# Sheet1_Auto_sedzia.net
KiCad netlist of a schematic drawn in Altium Designer
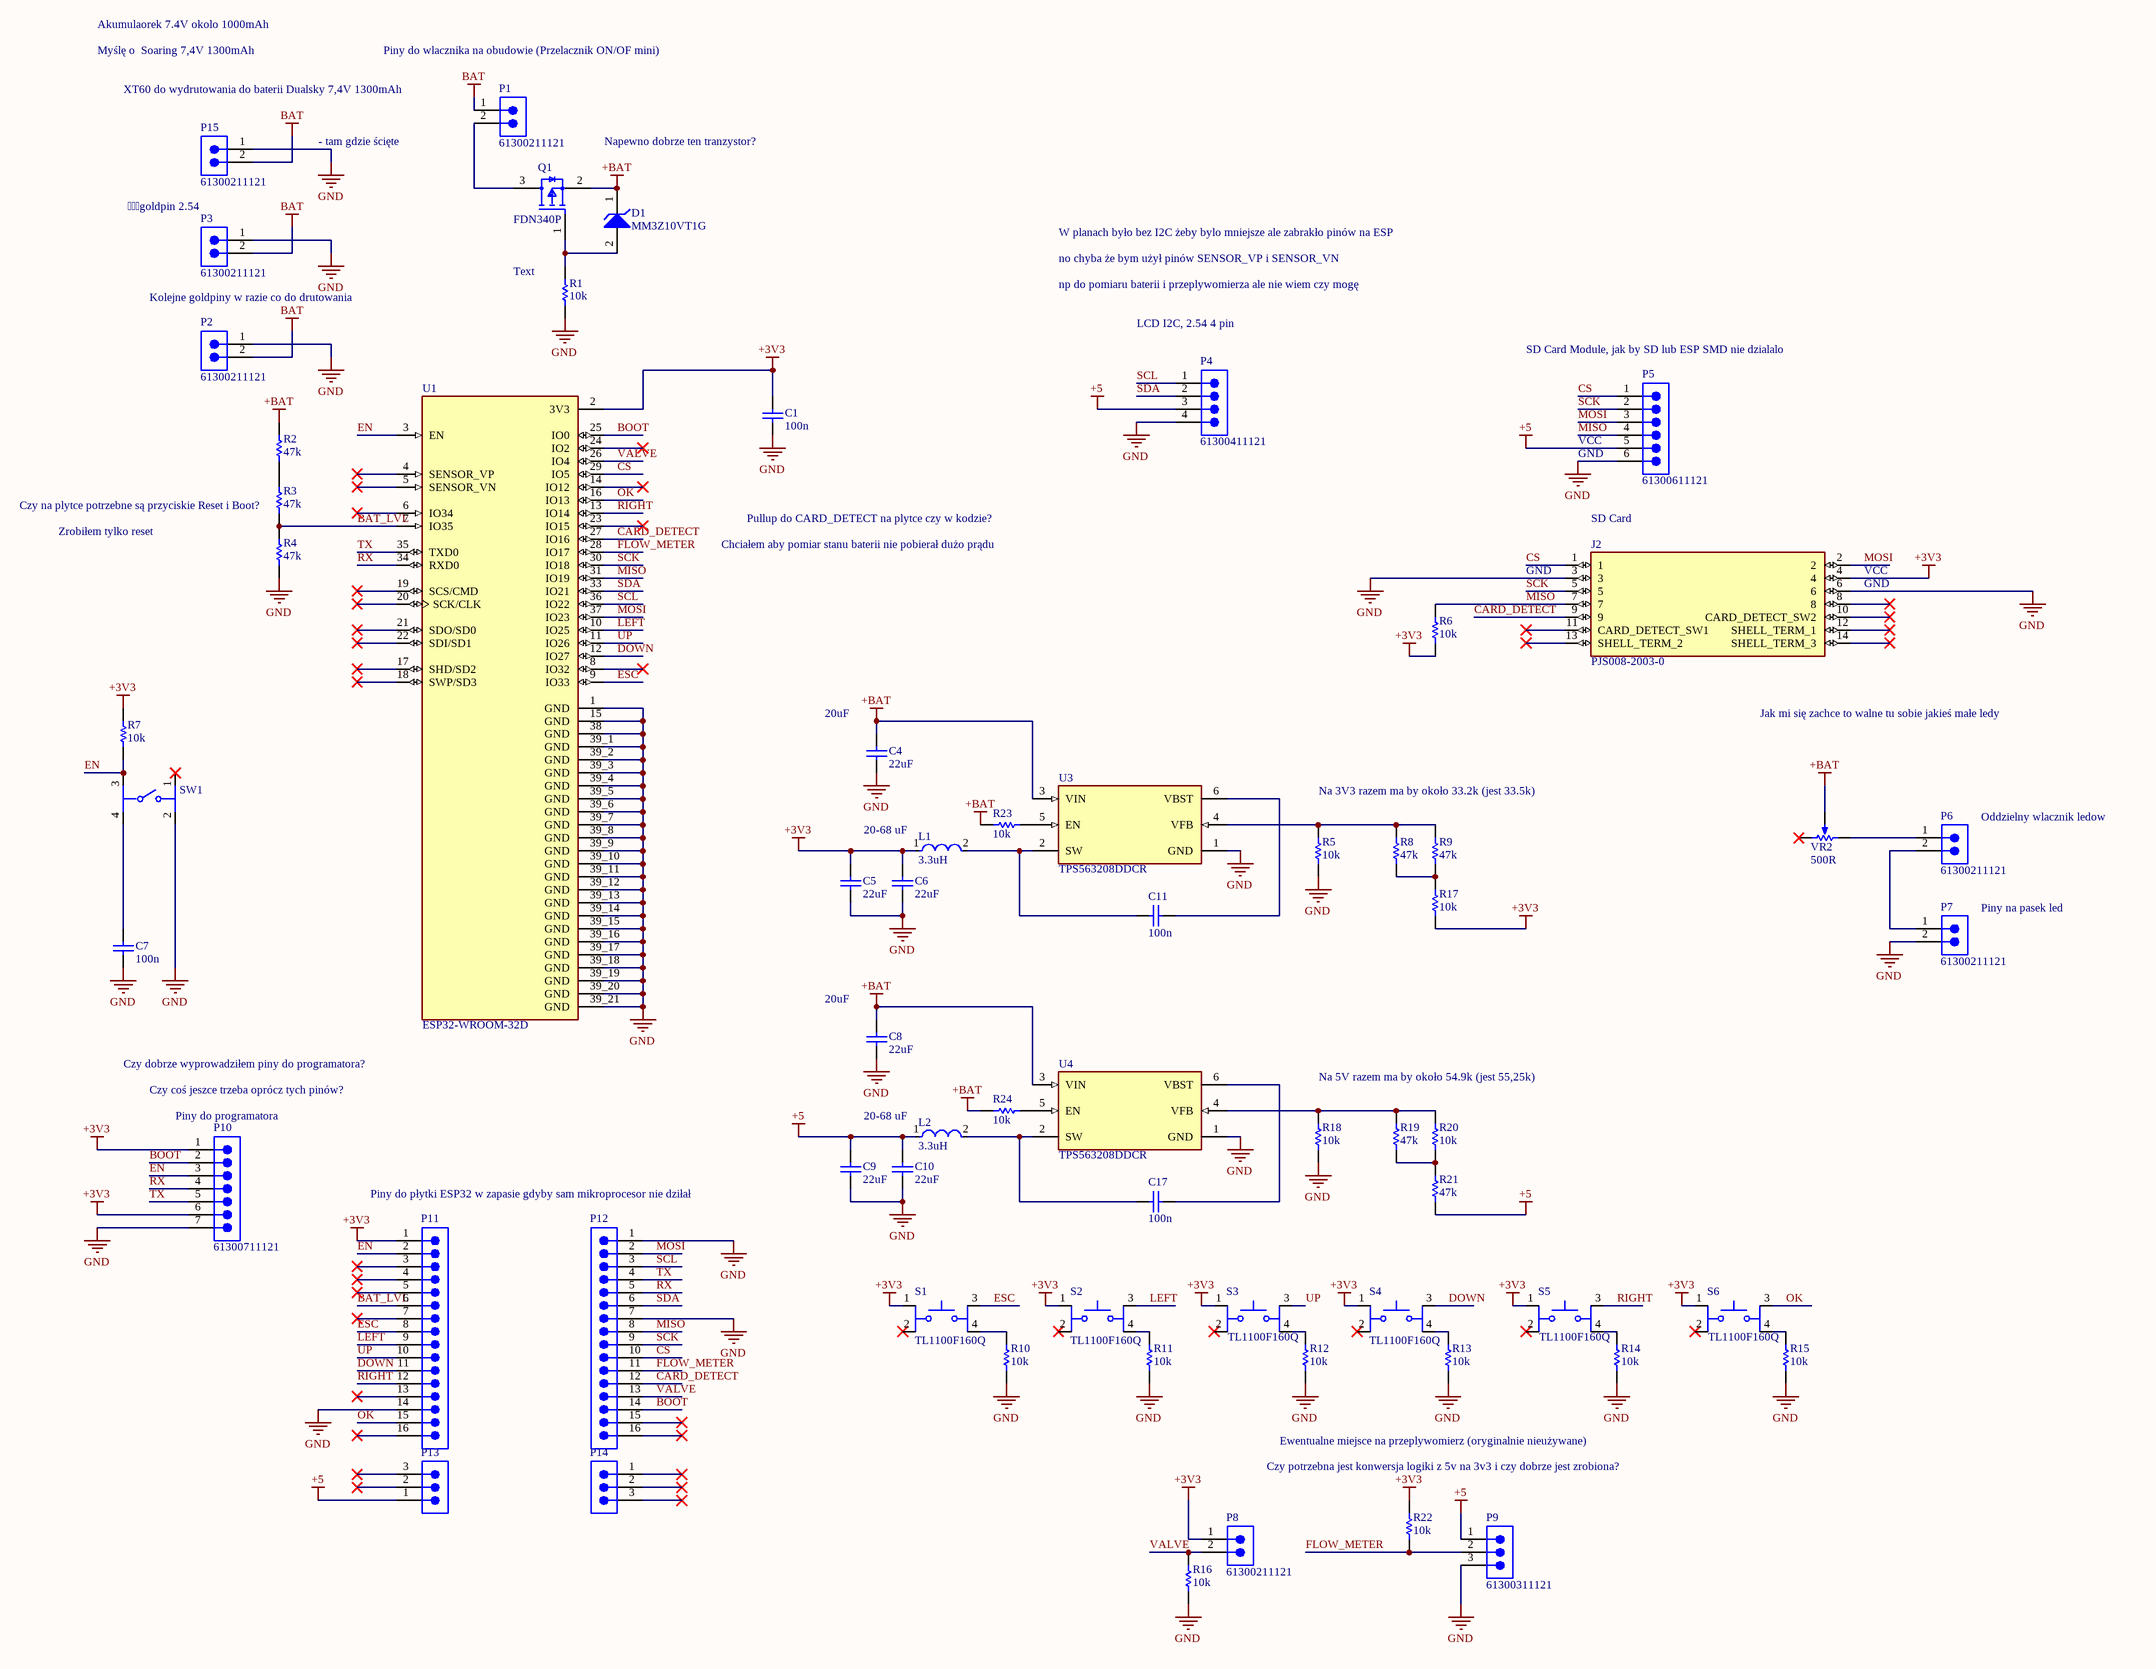
[diagram p0: Sheet1_Auto_sedzia.SchDoc]

(export (version "E")
  (design (tool "Eeschema 10.0.6"))
  (components
    (comp (ref "C1")
      (value "100n")
      (footprint "CAPC2013X88X50LL20T25")
      (description "0805")
      (fields (field (name "MANUFACTURER") "Kemet") (field (name "PART NUMBER") "C0805C103K5RACTU"))
      (libsource (lib "Altium Content Vault") (part "CAP"))
    )
    (comp (ref "C4")
      (value "22uF")
      (footprint "CAPC1608X100X20ML10")
      (description "Chip Capacitor, 22 uF, +/- 20%, 6.3 V, -55 to 85 degC, 1608 (0603 Metric), RoHS, Tape and Reel")
      (fields
        (field (name "TOLERANCE") "±20%")
        (field (name "PCN PART NUMBER") "MLCCPartNumberChange30/Nov/2012")
      )
      (libsource (lib "Altium Content Vault") (part "CAP-NP-2"))
    )
    (comp (ref "C5")
      (value "22uF")
      (footprint "CAPC1608X100X20ML10")
      (description "Chip Capacitor, 22 uF, +/- 20%, 6.3 V, -55 to 85 degC, 1608 (0603 Metric), RoHS, Tape and Reel")
      (fields
        (field (name "TOLERANCE") "±20%")
        (field (name "PCN PART NUMBER") "MLCCPartNumberChange30/Nov/2012")
      )
      (libsource (lib "Altium Content Vault") (part "CAP-NP-2"))
    )
    (comp (ref "C6")
      (value "22uF")
      (footprint "CAPC1608X100X20ML10")
      (description "Chip Capacitor, 22 uF, +/- 20%, 6.3 V, -55 to 85 degC, 1608 (0603 Metric), RoHS, Tape and Reel")
      (fields
        (field (name "TOLERANCE") "±20%")
        (field (name "PCN PART NUMBER") "MLCCPartNumberChange30/Nov/2012")
      )
      (libsource (lib "Altium Content Vault") (part "CAP-NP-2"))
    )
    (comp (ref "C7")
      (value "100n")
      (footprint "CAPC2013X88X50LL20T25")
      (description "0805")
      (fields (field (name "MANUFACTURER") "Kemet") (field (name "PART NUMBER") "C0805C103K5RACTU"))
      (libsource (lib "Altium Content Vault") (part "CAP"))
    )
    (comp (ref "C8")
      (value "22uF")
      (footprint "CAPC1608X100X20ML10")
      (description "Chip Capacitor, 22 uF, +/- 20%, 6.3 V, -55 to 85 degC, 1608 (0603 Metric), RoHS, Tape and Reel")
      (fields
        (field (name "TOLERANCE") "±20%")
        (field (name "PCN PART NUMBER") "MLCCPartNumberChange30/Nov/2012")
      )
      (libsource (lib "Altium Content Vault") (part "CAP-NP-2"))
    )
    (comp (ref "C9")
      (value "22uF")
      (footprint "CAPC1608X100X20ML10")
      (description "Chip Capacitor, 22 uF, +/- 20%, 6.3 V, -55 to 85 degC, 1608 (0603 Metric), RoHS, Tape and Reel")
      (fields
        (field (name "TOLERANCE") "±20%")
        (field (name "PCN PART NUMBER") "MLCCPartNumberChange30/Nov/2012")
      )
      (libsource (lib "Altium Content Vault") (part "CAP-NP-2"))
    )
    (comp (ref "C10")
      (value "22uF")
      (footprint "CAPC1608X100X20ML10")
      (description "Chip Capacitor, 22 uF, +/- 20%, 6.3 V, -55 to 85 degC, 1608 (0603 Metric), RoHS, Tape and Reel")
      (fields
        (field (name "TOLERANCE") "±20%")
        (field (name "PCN PART NUMBER") "MLCCPartNumberChange30/Nov/2012")
      )
      (libsource (lib "Altium Content Vault") (part "CAP-NP-2"))
    )
    (comp (ref "C11")
      (value "100n")
      (footprint "CAPC2013X88X50LL20T25")
      (description "0805")
      (fields (field (name "MANUFACTURER") "Kemet") (field (name "PART NUMBER") "C0805C103K5RACTU"))
      (libsource (lib "Altium Content Vault") (part "CAP"))
    )
    (comp (ref "C17")
      (value "100n")
      (footprint "CAPC2013X88X50LL20T25")
      (description "0805")
      (fields (field (name "MANUFACTURER") "Kemet") (field (name "PART NUMBER") "C0805C103K5RACTU"))
      (libsource (lib "Altium Content Vault") (part "CAP"))
    )
    (comp (ref "D1")
      (value "MM3Z10VT1G")
      (footprint "ONSC-SOD-323-2-477-02_V")
      (description "Zener Voltage Regulator, 300 mW, 2-Pin SOD-323, Pb-Free, Tape and Reel")
      (fields (field (name "MANUFACTURER") "On Semiconductor"))
      (libsource (lib "Altium Content Vault") (part "ONSC-K1A2-2"))
    )
    (comp (ref "J2")
      (value "PJS008-2003-0")
      (footprint "PJS008-2003-0")
      (description "Memory Card Connectors MicroSD Crd Conn SMT Revrs Mnt Push-Push")
      (fields (field (name "MF") "Yamaichi Electronics"))
      (libsource (lib "PJS008-2003-0") (part "PJS008-2003-0"))
    )
    (comp (ref "L1")
      (value "3.3uH")
      (footprint "FP-SRN6045-MFG")
      (description "FIXED IND 47UH 1.1A 257 MOHM SMD")
      (fields (field (name "TOLERANCE") "20%"))
      (libsource (lib "Altium Content Vault") (part "725321dda6339637d4d059423bc1c3c"))
    )
    (comp (ref "L2")
      (value "3.3uH")
      (footprint "FP-SRN6045-MFG")
      (description "FIXED IND 47UH 1.1A 257 MOHM SMD")
      (fields (field (name "TOLERANCE") "20%"))
      (libsource (lib "Altium Content Vault") (part "725321dda6339637d4d059423bc1c3c"))
    )
    (comp (ref "P1")
      (value "61300211121")
      (footprint "61300211121")
      (libsource (lib "Altium Content Vault") (part "Header_Male_1R_02P"))
    )
    (comp (ref "P2")
      (value "61300211121")
      (footprint "61300211121")
      (libsource (lib "Altium Content Vault") (part "Header_Male_1R_02P"))
    )
    (comp (ref "P3")
      (value "61300211121")
      (footprint "61300211121")
      (libsource (lib "Altium Content Vault") (part "Header_Male_1R_02P"))
    )
    (comp (ref "P4")
      (value "61300411121")
      (footprint "61300411121")
      (libsource (lib "Altium Content Vault") (part "Header_Male_1R_04P"))
    )
    (comp (ref "P5")
      (value "61300611121")
      (footprint "61300611121")
      (libsource (lib "Altium Content Vault") (part "Header_Male_1R_06P"))
    )
    (comp (ref "P6")
      (value "61300211121")
      (footprint "61300211121")
      (libsource (lib "Altium Content Vault") (part "Header_Male_1R_02P"))
    )
    (comp (ref "P7")
      (value "61300211121")
      (footprint "61300211121")
      (libsource (lib "Altium Content Vault") (part "Header_Male_1R_02P"))
    )
    (comp (ref "P8")
      (value "61300211121")
      (footprint "61300211121")
      (libsource (lib "Altium Content Vault") (part "Header_Male_1R_02P"))
    )
    (comp (ref "P9")
      (value "61300311121")
      (footprint "61300311121")
      (libsource (lib "Altium Content Vault") (part "Header_Male_1R_03P"))
    )
    (comp (ref "P10")
      (value "61300711121")
      (footprint "61300711121")
      (libsource (lib "Altium Content Vault") (part "Header_Male_1R_07P"))
    )
    (comp (ref "P11")
      (value "61301611121")
      (footprint "61301611121")
      (libsource (lib "Altium Content Vault") (part "Header_Male_1R_16P"))
    )
    (comp (ref "P12")
      (value "61301611121")
      (footprint "61301611121")
      (libsource (lib "Altium Content Vault") (part "Header_Male_1R_16P"))
    )
    (comp (ref "P13")
      (value "TSW-103-07-G-S")
      (footprint "SMTC-TSW-103-07-X-S")
      (description "0.025\" SQ Post Header, Through-hole, Vertical, -55 to 125 degC, 2.54 mm Pitch, 3-Pin, Male, RoHS")
      (fields (field (name "MANUFACTURER") "Samtec"))
      (libsource (lib "Altium Content Vault") (part "SMTC-TSW-103-X-X-S-X"))
    )
    (comp (ref "P14")
      (value "TSW-103-07-G-S")
      (footprint "SMTC-TSW-103-07-X-S")
      (description "0.025\" SQ Post Header, Through-hole, Vertical, -55 to 125 degC, 2.54 mm Pitch, 3-Pin, Male, RoHS")
      (fields (field (name "MANUFACTURER") "Samtec"))
      (libsource (lib "Altium Content Vault") (part "SMTC-TSW-103-X-X-S-X"))
    )
    (comp (ref "P15")
      (value "61300211121")
      (footprint "61300211121")
      (libsource (lib "Altium Content Vault") (part "Header_Male_1R_02P"))
    )
    (comp (ref "Q1")
      (value "FDN340P")
      (footprint "FP-527AG-MFG")
      (description "MOSFET P-CH 20V 2A SSOT3")
      (libsource (lib "Altium Content Vault") (part "d23f43cc42f60b967b7caccf14518fd"))
    )
    (comp (ref "R1")
      (value "10k")
      (footprint "RESC0805(2012)_L")
      (description "10K 0.125W 1% 0805 (2012 Metric)  SMD")
      (fields (field (name "TOLERANCE") "1 %") (field (name "POWER") "0.125 W"))
      (libsource (lib "Altium Content Vault") (part "RES"))
    )
    (comp (ref "R2")
      (value "47k")
      (footprint "RESC0805(2012)_L")
      (description "10K 0.125W 1% 0805 (2012 Metric)  SMD")
      (fields (field (name "TOLERANCE") "1 %") (field (name "POWER") "0.125 W"))
      (libsource (lib "Altium Content Vault") (part "RES"))
    )
    (comp (ref "R3")
      (value "47k")
      (footprint "RESC0805(2012)_L")
      (description "10K 0.125W 1% 0805 (2012 Metric)  SMD")
      (fields (field (name "TOLERANCE") "1 %") (field (name "POWER") "0.125 W"))
      (libsource (lib "Altium Content Vault") (part "RES"))
    )
    (comp (ref "R4")
      (value "47k")
      (footprint "RESC0805(2012)_L")
      (description "10K 0.125W 1% 0805 (2012 Metric)  SMD")
      (fields (field (name "TOLERANCE") "1 %") (field (name "POWER") "0.125 W"))
      (libsource (lib "Altium Content Vault") (part "RES"))
    )
    (comp (ref "R5")
      (value "10k")
      (footprint "RESC0805(2012)_L")
      (description "10K 0.125W 1% 0805 (2012 Metric)  SMD")
      (fields (field (name "TOLERANCE") "1 %") (field (name "POWER") "0.125 W"))
      (libsource (lib "Altium Content Vault") (part "RES"))
    )
    (comp (ref "R6")
      (value "10k")
      (footprint "RESC0805(2012)_L")
      (description "10K 0.125W 1% 0805 (2012 Metric)  SMD")
      (fields (field (name "TOLERANCE") "1 %") (field (name "POWER") "0.125 W"))
      (libsource (lib "Altium Content Vault") (part "RES"))
    )
    (comp (ref "R7")
      (value "10k")
      (footprint "RESC0805(2012)_L")
      (description "10K 0.125W 1% 0805 (2012 Metric)  SMD")
      (fields (field (name "TOLERANCE") "1 %") (field (name "POWER") "0.125 W"))
      (libsource (lib "Altium Content Vault") (part "RES"))
    )
    (comp (ref "R8")
      (value "47k")
      (footprint "RESC0805(2012)_L")
      (description "10K 0.125W 1% 0805 (2012 Metric)  SMD")
      (fields (field (name "TOLERANCE") "1 %") (field (name "POWER") "0.125 W"))
      (libsource (lib "Altium Content Vault") (part "RES"))
    )
    (comp (ref "R9")
      (value "47k")
      (footprint "RESC0805(2012)_L")
      (description "10K 0.125W 1% 0805 (2012 Metric)  SMD")
      (fields (field (name "TOLERANCE") "1 %") (field (name "POWER") "0.125 W"))
      (libsource (lib "Altium Content Vault") (part "RES"))
    )
    (comp (ref "R10")
      (value "10k")
      (footprint "RESC0805(2012)_L")
      (description "10K 0.125W 1% 0805 (2012 Metric)  SMD")
      (fields (field (name "TOLERANCE") "1 %") (field (name "POWER") "0.125 W"))
      (libsource (lib "Altium Content Vault") (part "RES"))
    )
    (comp (ref "R11")
      (value "10k")
      (footprint "RESC0805(2012)_L")
      (description "10K 0.125W 1% 0805 (2012 Metric)  SMD")
      (fields (field (name "TOLERANCE") "1 %") (field (name "POWER") "0.125 W"))
      (libsource (lib "Altium Content Vault") (part "RES"))
    )
    (comp (ref "R12")
      (value "10k")
      (footprint "RESC0805(2012)_L")
      (description "10K 0.125W 1% 0805 (2012 Metric)  SMD")
      (fields (field (name "TOLERANCE") "1 %") (field (name "POWER") "0.125 W"))
      (libsource (lib "Altium Content Vault") (part "RES"))
    )
    (comp (ref "R13")
      (value "10k")
      (footprint "RESC0805(2012)_L")
      (description "10K 0.125W 1% 0805 (2012 Metric)  SMD")
      (fields (field (name "TOLERANCE") "1 %") (field (name "POWER") "0.125 W"))
      (libsource (lib "Altium Content Vault") (part "RES"))
    )
    (comp (ref "R14")
      (value "10k")
      (footprint "RESC0805(2012)_L")
      (description "10K 0.125W 1% 0805 (2012 Metric)  SMD")
      (fields (field (name "TOLERANCE") "1 %") (field (name "POWER") "0.125 W"))
      (libsource (lib "Altium Content Vault") (part "RES"))
    )
    (comp (ref "R15")
      (value "10k")
      (footprint "RESC0805(2012)_L")
      (description "10K 0.125W 1% 0805 (2012 Metric)  SMD")
      (fields (field (name "TOLERANCE") "1 %") (field (name "POWER") "0.125 W"))
      (libsource (lib "Altium Content Vault") (part "RES"))
    )
    (comp (ref "R16")
      (value "10k")
      (footprint "RESC0805(2012)_L")
      (description "10K 0.125W 1% 0805 (2012 Metric)  SMD")
      (fields (field (name "TOLERANCE") "1 %") (field (name "POWER") "0.125 W"))
      (libsource (lib "Altium Content Vault") (part "RES"))
    )
    (comp (ref "R17")
      (value "10k")
      (footprint "RESC0805(2012)_L")
      (description "10K 0.125W 1% 0805 (2012 Metric)  SMD")
      (fields (field (name "TOLERANCE") "1 %") (field (name "POWER") "0.125 W"))
      (libsource (lib "Altium Content Vault") (part "RES"))
    )
    (comp (ref "R18")
      (value "10k")
      (footprint "RESC0805(2012)_L")
      (description "10K 0.125W 1% 0805 (2012 Metric)  SMD")
      (fields (field (name "TOLERANCE") "1 %") (field (name "POWER") "0.125 W"))
      (libsource (lib "Altium Content Vault") (part "RES"))
    )
    (comp (ref "R19")
      (value "47k")
      (footprint "RESC0805(2012)_L")
      (description "10K 0.125W 1% 0805 (2012 Metric)  SMD")
      (fields (field (name "TOLERANCE") "1 %") (field (name "POWER") "0.125 W"))
      (libsource (lib "Altium Content Vault") (part "RES"))
    )
    (comp (ref "R20")
      (value "10k")
      (footprint "RESC0805(2012)_L")
      (description "10K 0.125W 1% 0805 (2012 Metric)  SMD")
      (fields (field (name "TOLERANCE") "1 %") (field (name "POWER") "0.125 W"))
      (libsource (lib "Altium Content Vault") (part "RES"))
    )
    (comp (ref "R21")
      (value "47k")
      (footprint "RESC0805(2012)_L")
      (description "10K 0.125W 1% 0805 (2012 Metric)  SMD")
      (fields (field (name "TOLERANCE") "1 %") (field (name "POWER") "0.125 W"))
      (libsource (lib "Altium Content Vault") (part "RES"))
    )
    (comp (ref "R22")
      (value "10k")
      (footprint "RESC0805(2012)_L")
      (description "10K 0.125W 1% 0805 (2012 Metric)  SMD")
      (fields (field (name "TOLERANCE") "1 %") (field (name "POWER") "0.125 W"))
      (libsource (lib "Altium Content Vault") (part "RES"))
    )
    (comp (ref "R23")
      (value "10k")
      (footprint "RESC0805(2012)_L")
      (description "10K 0.125W 1% 0805 (2012 Metric)  SMD")
      (fields (field (name "TOLERANCE") "1 %") (field (name "POWER") "0.125 W"))
      (libsource (lib "Altium Content Vault") (part "RES"))
    )
    (comp (ref "R24")
      (value "10k")
      (footprint "RESC0805(2012)_L")
      (description "10K 0.125W 1% 0805 (2012 Metric)  SMD")
      (fields (field (name "TOLERANCE") "1 %") (field (name "POWER") "0.125 W"))
      (libsource (lib "Altium Content Vault") (part "RES"))
    )
    (comp (ref "S1")
      (value "TL1100F160Q")
      (footprint "SW_TL1100F160Q")
      (libsource (lib "TL1100F160Q") (part "TL1100F160Q"))
    )
    (comp (ref "S2")
      (value "TL1100F160Q")
      (footprint "SW_TL1100F160Q")
      (libsource (lib "TL1100F160Q") (part "TL1100F160Q"))
    )
    (comp (ref "S3")
      (value "TL1100F160Q")
      (footprint "SW_TL1100F160Q")
      (libsource (lib "TL1100F160Q") (part "TL1100F160Q"))
    )
    (comp (ref "S4")
      (value "TL1100F160Q")
      (footprint "SW_TL1100F160Q")
      (libsource (lib "TL1100F160Q") (part "TL1100F160Q"))
    )
    (comp (ref "S5")
      (value "TL1100F160Q")
      (footprint "SW_TL1100F160Q")
      (libsource (lib "TL1100F160Q") (part "TL1100F160Q"))
    )
    (comp (ref "S6")
      (value "TL1100F160Q")
      (footprint "SW_TL1100F160Q")
      (libsource (lib "TL1100F160Q") (part "TL1100F160Q"))
    )
    (comp (ref "SW1")
      (value "PTS645SM43SMTR92LFS")
      (footprint "FP-PTS645SM43SMTR92LFS-MFG")
      (description "SWITCH TACTILE SPST-NO 0.05A 12V")
      (libsource (lib "Altium Content Vault") (part "1adf0dd01260c80cf25a44bfd6b99ba"))
    )
    (comp (ref "U1")
      (value "ESP32-WROOM-32D")
      (footprint "MODULE_ESP32-WROOM-32D")
      (fields (field (name "MF") "Espressif Systems"))
      (libsource (lib "ESP32-WROOM-32D") (part "ESP32-WROOM-32D"))
    )
    (comp (ref "U3")
      (value "TPS563208DDCR")
      (footprint "FP-DDC0006A-MFG")
      (description "IC REG BUCK ADJ 3A TSOT23-6")
      (libsource (lib "Altium Content Vault") (part "aba72cbc9cf0ad42a1bc8855c06655c"))
    )
    (comp (ref "U4")
      (value "TPS563208DDCR")
      (footprint "FP-DDC0006A-MFG")
      (description "IC REG BUCK ADJ 3A TSOT23-6")
      (libsource (lib "Altium Content Vault") (part "aba72cbc9cf0ad42a1bc8855c06655c"))
    )
    (comp (ref "VR2")
      (value "500R")
      (footprint "BOUR-3362P")
      (description "Square Trimpot(R) Trimming Potentiometer, 10 KOhm, 300 V, -55 to 125 degC, 3-Pin THD, RoHS, Tube")
      (fields (field (name "TOLERANCE") "1%"))
      (libsource (lib "Altium Content Vault") (part "RES-POT-3"))
    )
  )
  (nets
    (net (code "1") (name "+3V3") (class "Default")
      (node (ref "C1") (pin "2") (pinfunction "2_2") (pintype "passive"))
      (node (ref "C5") (pin "2") (pinfunction "2_2") (pintype "passive"))
      (node (ref "C6") (pin "2") (pinfunction "2_2") (pintype "passive"))
      (node (ref "J2") (pin "4") (pinfunction "4_4") (pintype "bidirectional"))
      (node (ref "L1") (pin "1") (pinfunction "1_1") (pintype "passive"))
      (node (ref "P10") (pin "1") (pinfunction "1_1") (pintype "passive"))
      (node (ref "P10") (pin "6") (pinfunction "6_6") (pintype "passive"))
      (node (ref "P11") (pin "1") (pinfunction "1_1") (pintype "passive"))
      (node (ref "P8") (pin "1") (pinfunction "1_1") (pintype "passive"))
      (node (ref "R17") (pin "1") (pinfunction "1_1") (pintype "passive"))
      (node (ref "R22") (pin "2") (pinfunction "2_2") (pintype "passive"))
      (node (ref "R6") (pin "1") (pinfunction "1_1") (pintype "passive"))
      (node (ref "R7") (pin "2") (pinfunction "2_2") (pintype "passive"))
      (node (ref "S1") (pin "1") (pinfunction "1_1") (pintype "passive"))
      (node (ref "S2") (pin "1") (pinfunction "1_1") (pintype "passive"))
      (node (ref "S3") (pin "1") (pinfunction "1_1") (pintype "passive"))
      (node (ref "S4") (pin "1") (pinfunction "1_1") (pintype "passive"))
      (node (ref "S5") (pin "1") (pinfunction "1_1") (pintype "passive"))
      (node (ref "S6") (pin "1") (pinfunction "1_1") (pintype "passive"))
      (node (ref "U1") (pin "2") (pinfunction "3V3_2") (pintype "power_in"))
    )
    (net (code "2") (name "+5") (class "Default")
      (node (ref "C10") (pin "2") (pinfunction "2_2") (pintype "passive"))
      (node (ref "C9") (pin "2") (pinfunction "2_2") (pintype "passive"))
      (node (ref "L2") (pin "1") (pinfunction "1_1") (pintype "passive"))
      (node (ref "P13") (pin "1") (pinfunction "1_1") (pintype "passive"))
      (node (ref "P4") (pin "3") (pinfunction "3_3") (pintype "passive"))
      (node (ref "P5") (pin "5") (pinfunction "5_5") (pintype "passive"))
      (node (ref "P9") (pin "1") (pinfunction "1_1") (pintype "passive"))
      (node (ref "R21") (pin "1") (pinfunction "1_1") (pintype "passive"))
    )
    (net (code "3") (name "+BAT") (class "Default")
      (node (ref "C4") (pin "2") (pinfunction "2_2") (pintype "passive"))
      (node (ref "C8") (pin "2") (pinfunction "2_2") (pintype "passive"))
      (node (ref "D1") (pin "1") (pinfunction "K_1") (pintype "passive"))
      (node (ref "Q1") (pin "2") (pinfunction "S_2") (pintype "passive"))
      (node (ref "R2") (pin "2") (pinfunction "2_2") (pintype "passive"))
      (node (ref "R23") (pin "2") (pinfunction "2_2") (pintype "passive"))
      (node (ref "R24") (pin "2") (pinfunction "2_2") (pintype "passive"))
      (node (ref "U3") (pin "3") (pinfunction "VIN_3") (pintype "input"))
      (node (ref "U4") (pin "3") (pinfunction "VIN_3") (pintype "input"))
      (node (ref "VR2") (pin "2") (pinfunction "S_2") (pintype "passive"))
    )
    (net (code "4") (name "/BAT_LVL") (class "Default")
      (node (ref "P11") (pin "6") (pinfunction "6_6") (pintype "passive"))
      (node (ref "R3") (pin "1") (pinfunction "1_1") (pintype "passive"))
      (node (ref "R4") (pin "2") (pinfunction "2_2") (pintype "passive"))
      (node (ref "U1") (pin "7") (pinfunction "IO35_7") (pintype "input"))
    )
    (net (code "5") (name "/BOOT") (class "Default")
      (node (ref "P10") (pin "2") (pinfunction "2_2") (pintype "passive"))
      (node (ref "P12") (pin "14") (pinfunction "14_14") (pintype "passive"))
      (node (ref "U1") (pin "25") (pinfunction "IO0_25") (pintype "bidirectional"))
    )
    (net (code "6") (name "/CARD_DETECT") (class "Default")
      (node (ref "J2") (pin "9") (pinfunction "9_9") (pintype "bidirectional"))
      (node (ref "P12") (pin "12") (pinfunction "12_12") (pintype "passive"))
      (node (ref "U1") (pin "27") (pinfunction "IO16_27") (pintype "bidirectional"))
    )
    (net (code "7") (name "/CS") (class "Default")
      (node (ref "J2") (pin "1") (pinfunction "1_1") (pintype "bidirectional"))
      (node (ref "P12") (pin "10") (pinfunction "10_10") (pintype "passive"))
      (node (ref "P5") (pin "1") (pinfunction "1_1") (pintype "passive"))
      (node (ref "U1") (pin "29") (pinfunction "IO5_29") (pintype "bidirectional"))
    )
    (net (code "8") (name "/DOWN") (class "Default")
      (node (ref "P11") (pin "11") (pinfunction "11_11") (pintype "passive"))
      (node (ref "S4") (pin "3") (pinfunction "3_3") (pintype "passive"))
      (node (ref "U1") (pin "12") (pinfunction "IO27_12") (pintype "bidirectional"))
    )
    (net (code "9") (name "/EN") (class "Default")
      (node (ref "P10") (pin "3") (pinfunction "3_3") (pintype "passive"))
      (node (ref "P11") (pin "2") (pinfunction "2_2") (pintype "passive"))
      (node (ref "R7") (pin "1") (pinfunction "1_1") (pintype "passive"))
      (node (ref "SW1") (pin "3") (pinfunction "3_3") (pintype "passive"))
      (node (ref "U1") (pin "3") (pinfunction "EN_3") (pintype "input"))
    )
    (net (code "10") (name "/ESC") (class "Default")
      (node (ref "P11") (pin "8") (pinfunction "8_8") (pintype "passive"))
      (node (ref "S1") (pin "3") (pinfunction "3_3") (pintype "passive"))
      (node (ref "U1") (pin "9") (pinfunction "IO33_9") (pintype "bidirectional"))
    )
    (net (code "11") (name "/FLOW_METER") (class "Default")
      (node (ref "P12") (pin "11") (pinfunction "11_11") (pintype "passive"))
      (node (ref "P9") (pin "2") (pinfunction "2_2") (pintype "passive"))
      (node (ref "R22") (pin "1") (pinfunction "1_1") (pintype "passive"))
      (node (ref "U1") (pin "28") (pinfunction "IO17_28") (pintype "bidirectional"))
    )
    (net (code "12") (name "/LEFT") (class "Default")
      (node (ref "P11") (pin "9") (pinfunction "9_9") (pintype "passive"))
      (node (ref "S2") (pin "3") (pinfunction "3_3") (pintype "passive"))
      (node (ref "U1") (pin "10") (pinfunction "IO25_10") (pintype "bidirectional"))
    )
    (net (code "13") (name "/MISO") (class "Default")
      (node (ref "J2") (pin "7") (pinfunction "7_7") (pintype "bidirectional"))
      (node (ref "P12") (pin "8") (pinfunction "8_8") (pintype "passive"))
      (node (ref "P5") (pin "4") (pinfunction "4_4") (pintype "passive"))
      (node (ref "R6") (pin "2") (pinfunction "2_2") (pintype "passive"))
      (node (ref "U1") (pin "31") (pinfunction "IO19_31") (pintype "bidirectional"))
    )
    (net (code "14") (name "/MOSI") (class "Default")
      (node (ref "J2") (pin "2") (pinfunction "2_2") (pintype "bidirectional"))
      (node (ref "P12") (pin "2") (pinfunction "2_2") (pintype "passive"))
      (node (ref "P5") (pin "3") (pinfunction "3_3") (pintype "passive"))
      (node (ref "U1") (pin "37") (pinfunction "IO23_37") (pintype "bidirectional"))
    )
    (net (code "15") (name "/OK") (class "Default")
      (node (ref "P11") (pin "15") (pinfunction "15_15") (pintype "passive"))
      (node (ref "S6") (pin "3") (pinfunction "3_3") (pintype "passive"))
      (node (ref "U1") (pin "16") (pinfunction "IO13_16") (pintype "bidirectional"))
    )
    (net (code "16") (name "/RIGHT") (class "Default")
      (node (ref "P11") (pin "12") (pinfunction "12_12") (pintype "passive"))
      (node (ref "S5") (pin "3") (pinfunction "3_3") (pintype "passive"))
      (node (ref "U1") (pin "13") (pinfunction "IO14_13") (pintype "bidirectional"))
    )
    (net (code "17") (name "/RX") (class "Default")
      (node (ref "P10") (pin "4") (pinfunction "4_4") (pintype "passive"))
      (node (ref "P12") (pin "5") (pinfunction "5_5") (pintype "passive"))
      (node (ref "U1") (pin "34") (pinfunction "RXD0_34") (pintype "bidirectional"))
    )
    (net (code "18") (name "/SCK") (class "Default")
      (node (ref "J2") (pin "5") (pinfunction "5_5") (pintype "bidirectional"))
      (node (ref "P12") (pin "9") (pinfunction "9_9") (pintype "passive"))
      (node (ref "P5") (pin "2") (pinfunction "2_2") (pintype "passive"))
      (node (ref "U1") (pin "30") (pinfunction "IO18_30") (pintype "bidirectional"))
    )
    (net (code "19") (name "/SCL") (class "Default")
      (node (ref "P12") (pin "3") (pinfunction "3_3") (pintype "passive"))
      (node (ref "P4") (pin "1") (pinfunction "1_1") (pintype "passive"))
      (node (ref "U1") (pin "36") (pinfunction "IO22_36") (pintype "bidirectional"))
    )
    (net (code "20") (name "/SDA") (class "Default")
      (node (ref "P12") (pin "6") (pinfunction "6_6") (pintype "passive"))
      (node (ref "P4") (pin "2") (pinfunction "2_2") (pintype "passive"))
      (node (ref "U1") (pin "33") (pinfunction "IO21_33") (pintype "bidirectional"))
    )
    (net (code "21") (name "/TX") (class "Default")
      (node (ref "P10") (pin "5") (pinfunction "5_5") (pintype "passive"))
      (node (ref "P12") (pin "4") (pinfunction "4_4") (pintype "passive"))
      (node (ref "U1") (pin "35") (pinfunction "TXD0_35") (pintype "bidirectional"))
    )
    (net (code "22") (name "/UP") (class "Default")
      (node (ref "P11") (pin "10") (pinfunction "10_10") (pintype "passive"))
      (node (ref "S3") (pin "3") (pinfunction "3_3") (pintype "passive"))
      (node (ref "U1") (pin "11") (pinfunction "IO26_11") (pintype "bidirectional"))
    )
    (net (code "23") (name "/VALVE") (class "Default")
      (node (ref "P12") (pin "13") (pinfunction "13_13") (pintype "passive"))
      (node (ref "P8") (pin "2") (pinfunction "2_2") (pintype "passive"))
      (node (ref "R16") (pin "2") (pinfunction "2_2") (pintype "passive"))
      (node (ref "U1") (pin "26") (pinfunction "IO4_26") (pintype "bidirectional"))
    )
    (net (code "24") (name "BAT") (class "Default")
      (node (ref "P1") (pin "1") (pinfunction "1_1") (pintype "passive"))
      (node (ref "P15") (pin "2") (pinfunction "2_2") (pintype "passive"))
      (node (ref "P2") (pin "2") (pinfunction "2_2") (pintype "passive"))
      (node (ref "P3") (pin "2") (pinfunction "2_2") (pintype "passive"))
    )
    (net (code "25") (name "GND") (class "Default")
      (node (ref "C1") (pin "1") (pinfunction "1_1") (pintype "passive"))
      (node (ref "C10") (pin "1") (pinfunction "1_1") (pintype "passive"))
      (node (ref "C4") (pin "1") (pinfunction "1_1") (pintype "passive"))
      (node (ref "C5") (pin "1") (pinfunction "1_1") (pintype "passive"))
      (node (ref "C6") (pin "1") (pinfunction "1_1") (pintype "passive"))
      (node (ref "C7") (pin "1") (pinfunction "1_1") (pintype "passive"))
      (node (ref "C8") (pin "1") (pinfunction "1_1") (pintype "passive"))
      (node (ref "C9") (pin "1") (pinfunction "1_1") (pintype "passive"))
      (node (ref "J2") (pin "3") (pinfunction "3_3") (pintype "bidirectional"))
      (node (ref "J2") (pin "6") (pinfunction "6_6") (pintype "bidirectional"))
      (node (ref "P10") (pin "7") (pinfunction "7_7") (pintype "passive"))
      (node (ref "P11") (pin "14") (pinfunction "14_14") (pintype "passive"))
      (node (ref "P12") (pin "1") (pinfunction "1_1") (pintype "passive"))
      (node (ref "P12") (pin "7") (pinfunction "7_7") (pintype "passive"))
      (node (ref "P15") (pin "1") (pinfunction "1_1") (pintype "passive"))
      (node (ref "P2") (pin "1") (pinfunction "1_1") (pintype "passive"))
      (node (ref "P3") (pin "1") (pinfunction "1_1") (pintype "passive"))
      (node (ref "P4") (pin "4") (pinfunction "4_4") (pintype "passive"))
      (node (ref "P5") (pin "6") (pinfunction "6_6") (pintype "passive"))
      (node (ref "P7") (pin "2") (pinfunction "2_2") (pintype "passive"))
      (node (ref "P9") (pin "3") (pinfunction "3_3") (pintype "passive"))
      (node (ref "R1") (pin "1") (pinfunction "1_1") (pintype "passive"))
      (node (ref "R10") (pin "1") (pinfunction "1_1") (pintype "passive"))
      (node (ref "R11") (pin "1") (pinfunction "1_1") (pintype "passive"))
      (node (ref "R12") (pin "1") (pinfunction "1_1") (pintype "passive"))
      (node (ref "R13") (pin "1") (pinfunction "1_1") (pintype "passive"))
      (node (ref "R14") (pin "1") (pinfunction "1_1") (pintype "passive"))
      (node (ref "R15") (pin "1") (pinfunction "1_1") (pintype "passive"))
      (node (ref "R16") (pin "1") (pinfunction "1_1") (pintype "passive"))
      (node (ref "R18") (pin "1") (pinfunction "1_1") (pintype "passive"))
      (node (ref "R4") (pin "1") (pinfunction "1_1") (pintype "passive"))
      (node (ref "R5") (pin "1") (pinfunction "1_1") (pintype "passive"))
      (node (ref "SW1") (pin "2") (pinfunction "2_2") (pintype "passive"))
      (node (ref "U1") (pin "1") (pinfunction "GND_1") (pintype "power_in"))
      (node (ref "U1") (pin "15") (pinfunction "GND_15") (pintype "power_in"))
      (node (ref "U1") (pin "38") (pinfunction "GND_38") (pintype "power_in"))
      (node (ref "U1") (pin "39_1") (pinfunction "GND_39_1") (pintype "power_in"))
      (node (ref "U1") (pin "39_10") (pinfunction "GND_39_10") (pintype "power_in"))
      (node (ref "U1") (pin "39_11") (pinfunction "GND_39_11") (pintype "power_in"))
      (node (ref "U1") (pin "39_12") (pinfunction "GND_39_12") (pintype "power_in"))
      (node (ref "U1") (pin "39_13") (pinfunction "GND_39_13") (pintype "power_in"))
      (node (ref "U1") (pin "39_14") (pinfunction "GND_39_14") (pintype "power_in"))
      (node (ref "U1") (pin "39_15") (pinfunction "GND_39_15") (pintype "power_in"))
      (node (ref "U1") (pin "39_16") (pinfunction "GND_39_16") (pintype "power_in"))
      (node (ref "U1") (pin "39_17") (pinfunction "GND_39_17") (pintype "power_in"))
      (node (ref "U1") (pin "39_18") (pinfunction "GND_39_18") (pintype "power_in"))
      (node (ref "U1") (pin "39_19") (pinfunction "GND_39_19") (pintype "power_in"))
      (node (ref "U1") (pin "39_2") (pinfunction "GND_39_2") (pintype "power_in"))
      (node (ref "U1") (pin "39_20") (pinfunction "GND_39_20") (pintype "power_in"))
      (node (ref "U1") (pin "39_21") (pinfunction "GND_39_21") (pintype "power_in"))
      (node (ref "U1") (pin "39_3") (pinfunction "GND_39_3") (pintype "power_in"))
      (node (ref "U1") (pin "39_4") (pinfunction "GND_39_4") (pintype "power_in"))
      (node (ref "U1") (pin "39_5") (pinfunction "GND_39_5") (pintype "power_in"))
      (node (ref "U1") (pin "39_6") (pinfunction "GND_39_6") (pintype "power_in"))
      (node (ref "U1") (pin "39_7") (pinfunction "GND_39_7") (pintype "power_in"))
      (node (ref "U1") (pin "39_8") (pinfunction "GND_39_8") (pintype "power_in"))
      (node (ref "U1") (pin "39_9") (pinfunction "GND_39_9") (pintype "power_in"))
      (node (ref "U3") (pin "1") (pinfunction "GND_1") (pintype "power_in"))
      (node (ref "U4") (pin "1") (pinfunction "GND_1") (pintype "power_in"))
    )
    (net (code "26") (name "Net-(C7-Pad2)") (class "Default")
      (node (ref "C7") (pin "2") (pinfunction "2_2") (pintype "passive"))
      (node (ref "SW1") (pin "4") (pinfunction "4_4") (pintype "passive"))
    )
    (net (code "27") (name "Net-(D1-A)") (class "Default")
      (node (ref "D1") (pin "2") (pinfunction "A_2") (pintype "passive"))
      (node (ref "Q1") (pin "1") (pinfunction "G_1") (pintype "passive"))
      (node (ref "R1") (pin "2") (pinfunction "2_2") (pintype "passive"))
    )
    (net (code "28") (name "Net-(P6-Pad2)") (class "Default")
      (node (ref "P6") (pin "2") (pinfunction "2_2") (pintype "passive"))
      (node (ref "P7") (pin "1") (pinfunction "1_1") (pintype "passive"))
    )
    (net (code "29") (name "Net-(Q1-D)") (class "Default")
      (node (ref "P1") (pin "2") (pinfunction "2_2") (pintype "passive"))
      (node (ref "Q1") (pin "3") (pinfunction "D_3") (pintype "passive"))
    )
    (net (code "30") (name "Net-(R2-Pad1)") (class "Default")
      (node (ref "R2") (pin "1") (pinfunction "1_1") (pintype "passive"))
      (node (ref "R3") (pin "2") (pinfunction "2_2") (pintype "passive"))
    )
    (net (code "31") (name "Net-(R10-Pad2)") (class "Default")
      (node (ref "R10") (pin "2") (pinfunction "2_2") (pintype "passive"))
      (node (ref "S1") (pin "4") (pinfunction "4_4") (pintype "passive"))
    )
    (net (code "32") (name "Net-(R11-Pad2)") (class "Default")
      (node (ref "R11") (pin "2") (pinfunction "2_2") (pintype "passive"))
      (node (ref "S2") (pin "4") (pinfunction "4_4") (pintype "passive"))
    )
    (net (code "33") (name "Net-(R12-Pad2)") (class "Default")
      (node (ref "R12") (pin "2") (pinfunction "2_2") (pintype "passive"))
      (node (ref "S3") (pin "4") (pinfunction "4_4") (pintype "passive"))
    )
    (net (code "34") (name "Net-(R13-Pad2)") (class "Default")
      (node (ref "R13") (pin "2") (pinfunction "2_2") (pintype "passive"))
      (node (ref "S4") (pin "4") (pinfunction "4_4") (pintype "passive"))
    )
    (net (code "35") (name "Net-(R14-Pad2)") (class "Default")
      (node (ref "R14") (pin "2") (pinfunction "2_2") (pintype "passive"))
      (node (ref "S5") (pin "4") (pinfunction "4_4") (pintype "passive"))
    )
    (net (code "36") (name "Net-(R15-Pad2)") (class "Default")
      (node (ref "R15") (pin "2") (pinfunction "2_2") (pintype "passive"))
      (node (ref "S6") (pin "4") (pinfunction "4_4") (pintype "passive"))
    )
    (net (code "37") (name "Net-(R17-Pad2)") (class "Default")
      (node (ref "R17") (pin "2") (pinfunction "2_2") (pintype "passive"))
      (node (ref "R8") (pin "1") (pinfunction "1_1") (pintype "passive"))
      (node (ref "R9") (pin "1") (pinfunction "1_1") (pintype "passive"))
    )
    (net (code "38") (name "Net-(R19-Pad1)") (class "Default")
      (node (ref "R19") (pin "1") (pinfunction "1_1") (pintype "passive"))
      (node (ref "R20") (pin "1") (pinfunction "1_1") (pintype "passive"))
      (node (ref "R21") (pin "2") (pinfunction "2_2") (pintype "passive"))
    )
    (net (code "39") (name "Net-(U3-EN)") (class "Default")
      (node (ref "R23") (pin "1") (pinfunction "1_1") (pintype "passive"))
      (node (ref "U3") (pin "5") (pinfunction "EN_5") (pintype "input"))
    )
    (net (code "40") (name "Net-(U3-SW)") (class "Default")
      (node (ref "C11") (pin "2") (pinfunction "2_2") (pintype "passive"))
      (node (ref "L1") (pin "2") (pinfunction "2_2") (pintype "passive"))
      (node (ref "U3") (pin "2") (pinfunction "SW_2") (pintype "power_in"))
    )
    (net (code "41") (name "Net-(U3-VBST)") (class "Default")
      (node (ref "C11") (pin "1") (pinfunction "1_1") (pintype "passive"))
      (node (ref "U3") (pin "6") (pinfunction "VBST_6") (pintype "power_in"))
    )
    (net (code "42") (name "Net-(U3-VFB)") (class "Default")
      (node (ref "R5") (pin "2") (pinfunction "2_2") (pintype "passive"))
      (node (ref "R8") (pin "2") (pinfunction "2_2") (pintype "passive"))
      (node (ref "R9") (pin "2") (pinfunction "2_2") (pintype "passive"))
      (node (ref "U3") (pin "4") (pinfunction "VFB_4") (pintype "input"))
    )
    (net (code "43") (name "Net-(U4-EN)") (class "Default")
      (node (ref "R24") (pin "1") (pinfunction "1_1") (pintype "passive"))
      (node (ref "U4") (pin "5") (pinfunction "EN_5") (pintype "input"))
    )
    (net (code "44") (name "Net-(U4-SW)") (class "Default")
      (node (ref "C17") (pin "2") (pinfunction "2_2") (pintype "passive"))
      (node (ref "L2") (pin "2") (pinfunction "2_2") (pintype "passive"))
      (node (ref "U4") (pin "2") (pinfunction "SW_2") (pintype "power_in"))
    )
    (net (code "45") (name "Net-(U4-VBST)") (class "Default")
      (node (ref "C17") (pin "1") (pinfunction "1_1") (pintype "passive"))
      (node (ref "U4") (pin "6") (pinfunction "VBST_6") (pintype "power_in"))
    )
    (net (code "46") (name "Net-(U4-VFB)") (class "Default")
      (node (ref "R18") (pin "2") (pinfunction "2_2") (pintype "passive"))
      (node (ref "R19") (pin "2") (pinfunction "2_2") (pintype "passive"))
      (node (ref "R20") (pin "2") (pinfunction "2_2") (pintype "passive"))
      (node (ref "U4") (pin "4") (pinfunction "VFB_4") (pintype "input"))
    )
    (net (code "47") (name "Net-(VR2-CCW)") (class "Default")
      (node (ref "P6") (pin "1") (pinfunction "1_1") (pintype "passive"))
      (node (ref "VR2") (pin "1") (pinfunction "CCW_1") (pintype "passive"))
    )
    (net (code "48") (name "unconnected-(J2-CARD_DETECT_SW1-Pad11)") (class "Default")
      (node (ref "J2") (pin "11") (pinfunction "CARD_DETECT_SW1_11") (pintype "bidirectional+no_connect"))
    )
    (net (code "49") (name "unconnected-(J2-CARD_DETECT_SW2-Pad10)") (class "Default")
      (node (ref "J2") (pin "10") (pinfunction "CARD_DETECT_SW2_10") (pintype "bidirectional+no_connect"))
    )
    (net (code "50") (name "unconnected-(J2-Pad8)") (class "Default")
      (node (ref "J2") (pin "8") (pinfunction "8_8") (pintype "bidirectional+no_connect"))
    )
    (net (code "51") (name "unconnected-(J2-SHELL_TERM_1-Pad12)") (class "Default")
      (node (ref "J2") (pin "12") (pinfunction "SHELL_TERM_1_12") (pintype "bidirectional+no_connect"))
    )
    (net (code "52") (name "unconnected-(J2-SHELL_TERM_2-Pad13)") (class "Default")
      (node (ref "J2") (pin "13") (pinfunction "SHELL_TERM_2_13") (pintype "bidirectional+no_connect"))
    )
    (net (code "53") (name "unconnected-(J2-SHELL_TERM_3-Pad14)") (class "Default")
      (node (ref "J2") (pin "14") (pinfunction "SHELL_TERM_3_14") (pintype "bidirectional+no_connect"))
    )
    (net (code "54") (name "unconnected-(P11-Pad3)") (class "Default")
      (node (ref "P11") (pin "3") (pinfunction "3_3") (pintype "passive+no_connect"))
    )
    (net (code "55") (name "unconnected-(P11-Pad4)") (class "Default")
      (node (ref "P11") (pin "4") (pinfunction "4_4") (pintype "passive+no_connect"))
    )
    (net (code "56") (name "unconnected-(P11-Pad5)") (class "Default")
      (node (ref "P11") (pin "5") (pinfunction "5_5") (pintype "passive+no_connect"))
    )
    (net (code "57") (name "unconnected-(P11-Pad7)") (class "Default")
      (node (ref "P11") (pin "7") (pinfunction "7_7") (pintype "passive+no_connect"))
    )
    (net (code "58") (name "unconnected-(P11-Pad13)") (class "Default")
      (node (ref "P11") (pin "13") (pinfunction "13_13") (pintype "passive+no_connect"))
    )
    (net (code "59") (name "unconnected-(P11-Pad16)") (class "Default")
      (node (ref "P11") (pin "16") (pinfunction "16_16") (pintype "passive+no_connect"))
    )
    (net (code "60") (name "unconnected-(P12-Pad15)") (class "Default")
      (node (ref "P12") (pin "15") (pinfunction "15_15") (pintype "passive+no_connect"))
    )
    (net (code "61") (name "unconnected-(P12-Pad16)") (class "Default")
      (node (ref "P12") (pin "16") (pinfunction "16_16") (pintype "passive+no_connect"))
    )
    (net (code "62") (name "unconnected-(P13-Pad2)") (class "Default")
      (node (ref "P13") (pin "2") (pinfunction "2_2") (pintype "passive+no_connect"))
    )
    (net (code "63") (name "unconnected-(P13-Pad3)") (class "Default")
      (node (ref "P13") (pin "3") (pinfunction "3_3") (pintype "passive+no_connect"))
    )
    (net (code "64") (name "unconnected-(P14-Pad1)") (class "Default")
      (node (ref "P14") (pin "1") (pinfunction "1_1") (pintype "passive+no_connect"))
    )
    (net (code "65") (name "unconnected-(P14-Pad2)") (class "Default")
      (node (ref "P14") (pin "2") (pinfunction "2_2") (pintype "passive+no_connect"))
    )
    (net (code "66") (name "unconnected-(P14-Pad3)") (class "Default")
      (node (ref "P14") (pin "3") (pinfunction "3_3") (pintype "passive+no_connect"))
    )
    (net (code "67") (name "unconnected-(S1-Pad2)") (class "Default")
      (node (ref "S1") (pin "2") (pinfunction "2_2") (pintype "passive+no_connect"))
    )
    (net (code "68") (name "unconnected-(S2-Pad2)") (class "Default")
      (node (ref "S2") (pin "2") (pinfunction "2_2") (pintype "passive+no_connect"))
    )
    (net (code "69") (name "unconnected-(S3-Pad2)") (class "Default")
      (node (ref "S3") (pin "2") (pinfunction "2_2") (pintype "passive+no_connect"))
    )
    (net (code "70") (name "unconnected-(S4-Pad2)") (class "Default")
      (node (ref "S4") (pin "2") (pinfunction "2_2") (pintype "passive+no_connect"))
    )
    (net (code "71") (name "unconnected-(S5-Pad2)") (class "Default")
      (node (ref "S5") (pin "2") (pinfunction "2_2") (pintype "passive+no_connect"))
    )
    (net (code "72") (name "unconnected-(S6-Pad2)") (class "Default")
      (node (ref "S6") (pin "2") (pinfunction "2_2") (pintype "passive+no_connect"))
    )
    (net (code "73") (name "unconnected-(SW1-Pad1)") (class "Default")
      (node (ref "SW1") (pin "1") (pinfunction "1_1") (pintype "passive+no_connect"))
    )
    (net (code "74") (name "unconnected-(U1-IO2-Pad24)") (class "Default")
      (node (ref "U1") (pin "24") (pinfunction "IO2_24") (pintype "bidirectional+no_connect"))
    )
    (net (code "75") (name "unconnected-(U1-IO12-Pad14)") (class "Default")
      (node (ref "U1") (pin "14") (pinfunction "IO12_14") (pintype "bidirectional+no_connect"))
    )
    (net (code "76") (name "unconnected-(U1-IO15-Pad23)") (class "Default")
      (node (ref "U1") (pin "23") (pinfunction "IO15_23") (pintype "bidirectional+no_connect"))
    )
    (net (code "77") (name "unconnected-(U1-IO32-Pad8)") (class "Default")
      (node (ref "U1") (pin "8") (pinfunction "IO32_8") (pintype "bidirectional+no_connect"))
    )
    (net (code "78") (name "unconnected-(U1-IO34-Pad6)") (class "Default")
      (node (ref "U1") (pin "6") (pinfunction "IO34_6") (pintype "input+no_connect"))
    )
    (net (code "79") (name "unconnected-(U1-SCK{slash}CLK-Pad20)") (class "Default")
      (node (ref "U1") (pin "20") (pinfunction "SCK/CLK_20") (pintype "bidirectional+no_connect"))
    )
    (net (code "80") (name "unconnected-(U1-SCS{slash}CMD-Pad19)") (class "Default")
      (node (ref "U1") (pin "19") (pinfunction "SCS/CMD_19") (pintype "bidirectional+no_connect"))
    )
    (net (code "81") (name "unconnected-(U1-SDI{slash}SD1-Pad22)") (class "Default")
      (node (ref "U1") (pin "22") (pinfunction "SDI/SD1_22") (pintype "bidirectional+no_connect"))
    )
    (net (code "82") (name "unconnected-(U1-SDO{slash}SD0-Pad21)") (class "Default")
      (node (ref "U1") (pin "21") (pinfunction "SDO/SD0_21") (pintype "bidirectional+no_connect"))
    )
    (net (code "83") (name "unconnected-(U1-SENSOR_VN-Pad5)") (class "Default")
      (node (ref "U1") (pin "5") (pinfunction "SENSOR_VN_5") (pintype "input+no_connect"))
    )
    (net (code "84") (name "unconnected-(U1-SENSOR_VP-Pad4)") (class "Default")
      (node (ref "U1") (pin "4") (pinfunction "SENSOR_VP_4") (pintype "input+no_connect"))
    )
    (net (code "85") (name "unconnected-(U1-SHD{slash}SD2-Pad17)") (class "Default")
      (node (ref "U1") (pin "17") (pinfunction "SHD/SD2_17") (pintype "bidirectional+no_connect"))
    )
    (net (code "86") (name "unconnected-(U1-SWP{slash}SD3-Pad18)") (class "Default")
      (node (ref "U1") (pin "18") (pinfunction "SWP/SD3_18") (pintype "bidirectional+no_connect"))
    )
    (net (code "87") (name "unconnected-(VR2-CW-Pad3)") (class "Default")
      (node (ref "VR2") (pin "3") (pinfunction "CW_3") (pintype "passive+no_connect"))
    )
  )
)
